# butt_blaster_mk_3.net
KiCad netlist of a schematic drawn in EAGLE
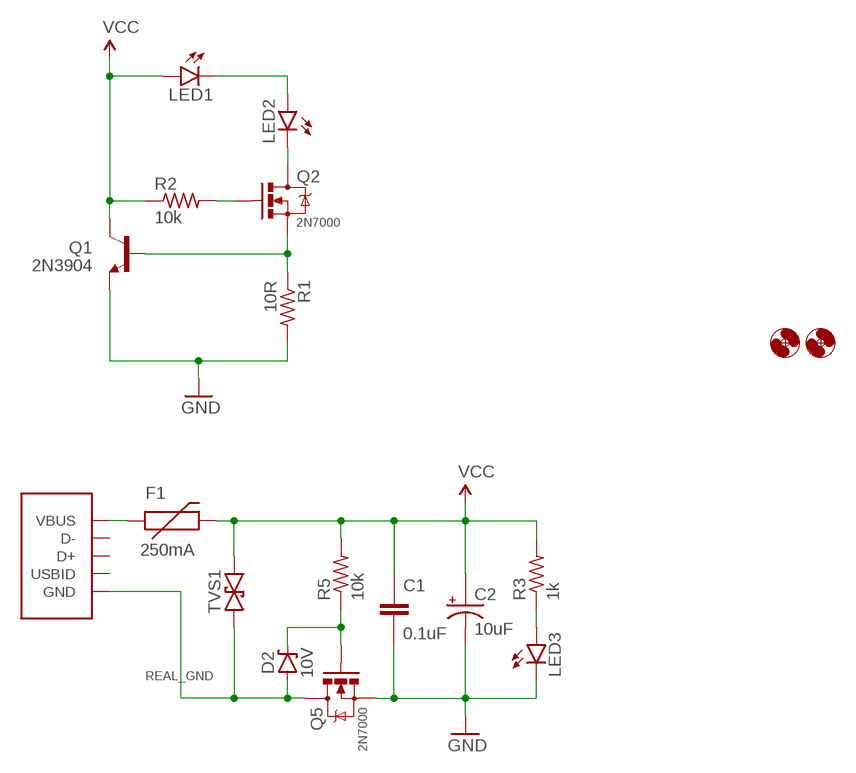
[diagram p0: schematic, sheet 1]

(export (version "E")
  (design (tool "Eeschema 10.0.6"))
  (components
    (comp (ref "C1")
      (value "0.1uF")
      (footprint "eagle-import:C025-024X044")
      (libsource (lib "eagle-import") (part "CAPACITOR-CERAMIC025-024X044"))
    )
    (comp (ref "C2")
      (value "10uF")
      (footprint "eagle-import:E2,5-6")
      (libsource (lib "eagle-import") (part "CAPACITOR-POLARIZEDE2.5-6"))
    )
    (comp (ref "D2")
      (value "10V")
      (footprint "eagle-import:DIODE-7.68MM")
      (libsource (lib "eagle-import") (part "DIODE-ZENERPTH-7.68MM"))
    )
    (comp (ref "F1")
      (value "250mA")
      (footprint "eagle-import:PTC")
      (libsource (lib "eagle-import") (part "PTCPTH"))
    )
    (comp (ref "H1")
      (value "HOLE#2")
      (footprint "eagle-import:HOLE-#2")
      (libsource (lib "eagle-import") (part "HOLE#2"))
    )
    (comp (ref "H2")
      (value "HOLE#2")
      (footprint "eagle-import:HOLE-#2")
      (libsource (lib "eagle-import") (part "HOLE#2"))
    )
    (comp (ref "LED1")
      (value "LED5MM_SHORTPADS")
      (footprint "eagle-import:LED5MM_SHORTPADS")
      (libsource (lib "eagle-import") (part "LED5MM_SHORTPADS"))
    )
    (comp (ref "LED2")
      (value "LED5MM_SHORTPADS")
      (footprint "eagle-import:LED5MM_SHORTPADS")
      (libsource (lib "eagle-import") (part "LED5MM_SHORTPADS"))
    )
    (comp (ref "LED3")
      (value "LED3MM")
      (footprint "eagle-import:LED3MM")
      (libsource (lib "eagle-import") (part "LED3MM"))
    )
    (comp (ref "PWR")
      (value "USB-ABCOMBO")
      (footprint "eagle-import:USB-MICRO-B-FCI-CUTOUT")
      (libsource (lib "eagle-import") (part "USB-ABCOMBO"))
    )
    (comp (ref "Q1")
      (value "2N3904")
      (footprint "eagle-import:TO-92-AMMO")
      (libsource (lib "eagle-import") (part "TRANSISTOR_NPNTO-92-AMMO-EBC"))
    )
    (comp (ref "Q2")
      (value "2N7000")
      (footprint "eagle-import:TO-92-AMMO")
      (libsource (lib "eagle-import") (part "MOSFET-NCHANNEL2N7000-AMMO"))
    )
    (comp (ref "Q5")
      (value "2N7000")
      (footprint "eagle-import:TO-92-AMMO")
      (libsource (lib "eagle-import") (part "MOSFET-NCHANNEL2N7000-AMMO"))
    )
    (comp (ref "R1")
      (value "10R")
      (footprint "eagle-import:RESISTOR-AXIAL-PTH-10.16MM")
      (libsource (lib "eagle-import") (part "RESISTORPTH-AXIAL-10.16MM"))
    )
    (comp (ref "R2")
      (value "10k")
      (footprint "eagle-import:RESISTOR-AXIAL-PTH-6.35MM")
      (libsource (lib "eagle-import") (part "RESISTORPTH-AXIAL-6.35MM"))
    )
    (comp (ref "R3")
      (value "1k")
      (footprint "eagle-import:RESISTOR-AXIAL-PTH-6.35MM")
      (libsource (lib "eagle-import") (part "RESISTORPTH-AXIAL-6.35MM"))
    )
    (comp (ref "R5")
      (value "10k")
      (footprint "eagle-import:RESISTOR-AXIAL-PTH-7.68MM")
      (libsource (lib "eagle-import") (part "RESISTORPTH-AXIAL-7.68MM"))
    )
    (comp (ref "TVS1")
      (value "TVSDO-41-TVS-BIDIRECTIONAL")
      (footprint "eagle-import:DO-41-TVS")
      (libsource (lib "eagle-import") (part "TVSDO-41-TVS-BIDIRECTIONAL"))
    )
  )
  (nets
    (net (code "1") (name "/REAL_GND") (class "Default")
      (node (ref "D2") (pin "A") (pinfunction "A_A") (pintype "passive"))
      (node (ref "PWR") (pin "5") (pinfunction "GND_5") (pintype "bidirectional"))
      (node (ref "PWR") (pin "P$1") (pinfunction "GND_P$1") (pintype "bidirectional"))
      (node (ref "PWR") (pin "P$2") (pinfunction "GND_P$2") (pintype "bidirectional"))
      (node (ref "Q5") (pin "3") (pinfunction "D_3") (pintype "passive"))
      (node (ref "TVS1") (pin "P$1") (pinfunction "1_P$1") (pintype "passive"))
    )
    (net (code "2") (name "GND") (class "Default")
      (node (ref "C1") (pin "2") (pinfunction "2_2") (pintype "passive"))
      (node (ref "C2") (pin "-") (pinfunction "-_-") (pintype "passive"))
      (node (ref "LED3") (pin "K") (pinfunction "C_K") (pintype "passive"))
      (node (ref "Q1") (pin "1") (pinfunction "E_1") (pintype "passive"))
      (node (ref "Q5") (pin "1") (pinfunction "S_1") (pintype "passive"))
      (node (ref "R1") (pin "P$2") (pinfunction "2_P$2") (pintype "passive"))
    )
    (net (code "3") (name "Net-(D2-C)") (class "Default")
      (node (ref "D2") (pin "K") (pinfunction "C_K") (pintype "passive"))
      (node (ref "Q5") (pin "2") (pinfunction "G_2") (pintype "passive"))
      (node (ref "R5") (pin "P$1") (pinfunction "1_P$1") (pintype "passive"))
    )
    (net (code "4") (name "Net-(F1-1)") (class "Default")
      (node (ref "F1") (pin "P$1") (pinfunction "1_P$1") (pintype "bidirectional"))
      (node (ref "PWR") (pin "1") (pinfunction "VBUS_1") (pintype "bidirectional"))
    )
    (net (code "5") (name "Net-(LED1-C)") (class "Default")
      (node (ref "LED1") (pin "K") (pinfunction "C_K") (pintype "passive"))
      (node (ref "LED2") (pin "A") (pinfunction "A_A") (pintype "passive"))
    )
    (net (code "6") (name "Net-(LED2-C)") (class "Default")
      (node (ref "LED2") (pin "K") (pinfunction "C_K") (pintype "passive"))
      (node (ref "Q2") (pin "3") (pinfunction "D_3") (pintype "passive"))
    )
    (net (code "7") (name "Net-(Q1-B)") (class "Default")
      (node (ref "Q1") (pin "2") (pinfunction "B_2") (pintype "passive"))
      (node (ref "Q2") (pin "1") (pinfunction "S_1") (pintype "passive"))
      (node (ref "R1") (pin "P$1") (pinfunction "1_P$1") (pintype "passive"))
    )
    (net (code "8") (name "Net-(Q2-G)") (class "Default")
      (node (ref "Q2") (pin "2") (pinfunction "G_2") (pintype "passive"))
      (node (ref "R2") (pin "P$2") (pinfunction "2_P$2") (pintype "passive"))
    )
    (net (code "9") (name "Net-(R3-1)") (class "Default")
      (node (ref "LED3") (pin "A") (pinfunction "A_A") (pintype "passive"))
      (node (ref "R3") (pin "P$1") (pinfunction "1_P$1") (pintype "passive"))
    )
    (net (code "10") (name "VCC") (class "Default")
      (node (ref "C1") (pin "1") (pinfunction "1_1") (pintype "passive"))
      (node (ref "C2") (pin "+") (pinfunction "+_+") (pintype "passive"))
      (node (ref "F1") (pin "P$2") (pinfunction "2_P$2") (pintype "bidirectional"))
      (node (ref "LED1") (pin "A") (pinfunction "A_A") (pintype "passive"))
      (node (ref "Q1") (pin "3") (pinfunction "C_3") (pintype "passive"))
      (node (ref "R2") (pin "P$1") (pinfunction "1_P$1") (pintype "passive"))
      (node (ref "R3") (pin "P$2") (pinfunction "2_P$2") (pintype "passive"))
      (node (ref "R5") (pin "P$2") (pinfunction "2_P$2") (pintype "passive"))
      (node (ref "TVS1") (pin "P$2") (pinfunction "2_P$2") (pintype "passive"))
    )
    (net (code "11") (name "unconnected-(PWR-D+-Pad3)") (class "Default")
      (node (ref "PWR") (pin "3") (pinfunction "D+_3") (pintype "bidirectional"))
    )
    (net (code "12") (name "unconnected-(PWR-D--Pad2)") (class "Default")
      (node (ref "PWR") (pin "2") (pinfunction "D-_2") (pintype "bidirectional"))
    )
    (net (code "13") (name "unconnected-(PWR-USBID-Pad4)") (class "Default")
      (node (ref "PWR") (pin "4") (pinfunction "USBID_4") (pintype "bidirectional"))
    )
  )
)
